# TA-1042-8P8C_V5.net
KiCad netlist of a schematic drawn in EAGLE
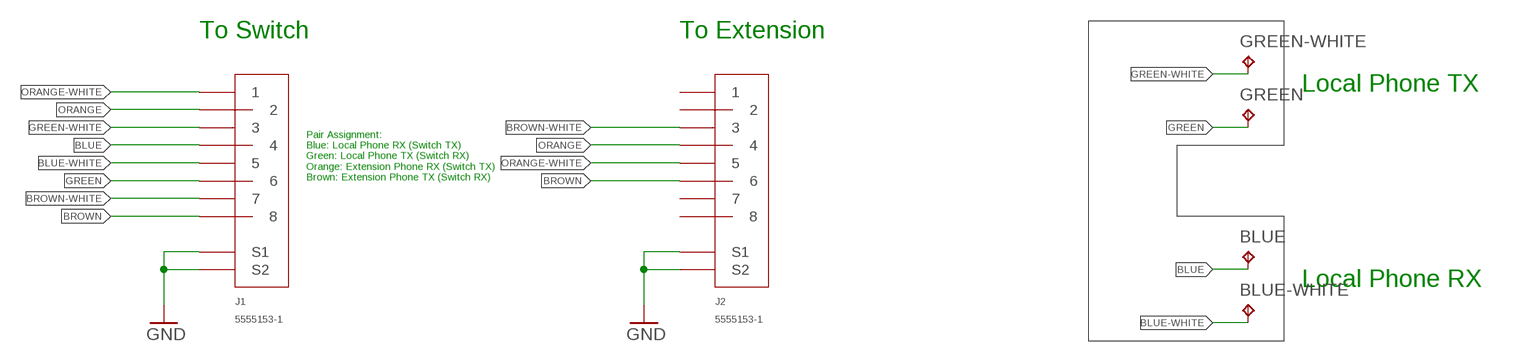
[diagram p0: schematic, sheet 1]

(export (version "E")
  (design (tool "Eeschema 10.0.6"))
  (components
    (comp (ref "BLUE")
      (value "TPTP20R")
      (footprint "eagle-import:TP20R")
      (libsource (lib "eagle-import") (part "TPTP20R"))
    )
    (comp (ref "BLUE-WHITE")
      (value "TPTP20R")
      (footprint "eagle-import:TP20R")
      (libsource (lib "eagle-import") (part "TPTP20R"))
    )
    (comp (ref "GREEN")
      (value "TPTP20R")
      (footprint "eagle-import:TP20R")
      (libsource (lib "eagle-import") (part "TPTP20R"))
    )
    (comp (ref "GREEN-WHITE")
      (value "TPTP20R")
      (footprint "eagle-import:TP20R")
      (libsource (lib "eagle-import") (part "TPTP20R"))
    )
    (comp (ref "J1")
      (value "5555153-1")
      (footprint "eagle-import:5555153-1")
      (fields (field (name "PARTNO") "A31438-ND"))
      (libsource (lib "eagle-import") (part "5555153-1"))
    )
    (comp (ref "J2")
      (value "5555153-1")
      (footprint "eagle-import:5555153-1")
      (fields (field (name "PARTNO") "A31438-ND"))
      (libsource (lib "eagle-import") (part "5555153-1"))
    )
  )
  (nets
    (net (code "1") (name "BLUE") (class "Default")
      (node (ref "BLUE") (pin "TP") (pinfunction "TP_TP") (pintype "input"))
      (node (ref "J1") (pin "4") (pinfunction "4_4") (pintype "bidirectional"))
    )
    (net (code "2") (name "BLUE-WHITE") (class "Default")
      (node (ref "BLUE-WHITE") (pin "TP") (pinfunction "TP_TP") (pintype "input"))
      (node (ref "J1") (pin "5") (pinfunction "5_5") (pintype "bidirectional"))
    )
    (net (code "3") (name "BROWN") (class "Default")
      (node (ref "J1") (pin "8") (pinfunction "8_8") (pintype "bidirectional"))
      (node (ref "J2") (pin "6") (pinfunction "6_6") (pintype "bidirectional"))
    )
    (net (code "4") (name "BROWN-WHITE") (class "Default")
      (node (ref "J1") (pin "7") (pinfunction "7_7") (pintype "bidirectional"))
      (node (ref "J2") (pin "3") (pinfunction "3_3") (pintype "bidirectional"))
    )
    (net (code "5") (name "GND") (class "Default")
      (node (ref "J1") (pin "S1") (pinfunction "S1_S1") (pintype "bidirectional"))
      (node (ref "J1") (pin "S2") (pinfunction "S2_S2") (pintype "bidirectional"))
      (node (ref "J2") (pin "S1") (pinfunction "S1_S1") (pintype "bidirectional"))
      (node (ref "J2") (pin "S2") (pinfunction "S2_S2") (pintype "bidirectional"))
    )
    (net (code "6") (name "GREEN") (class "Default")
      (node (ref "GREEN") (pin "TP") (pinfunction "TP_TP") (pintype "input"))
      (node (ref "J1") (pin "6") (pinfunction "6_6") (pintype "bidirectional"))
    )
    (net (code "7") (name "GREEN-WHITE") (class "Default")
      (node (ref "GREEN-WHITE") (pin "TP") (pinfunction "TP_TP") (pintype "input"))
      (node (ref "J1") (pin "3") (pinfunction "3_3") (pintype "bidirectional"))
    )
    (net (code "8") (name "ORANGE") (class "Default")
      (node (ref "J1") (pin "2") (pinfunction "2_2") (pintype "bidirectional"))
      (node (ref "J2") (pin "4") (pinfunction "4_4") (pintype "bidirectional"))
    )
    (net (code "9") (name "ORANGE-WHITE") (class "Default")
      (node (ref "J1") (pin "1") (pinfunction "1_1") (pintype "bidirectional"))
      (node (ref "J2") (pin "5") (pinfunction "5_5") (pintype "bidirectional"))
    )
    (net (code "10") (name "unconnected-(J2-Pad1)") (class "Default")
      (node (ref "J2") (pin "1") (pinfunction "1_1") (pintype "bidirectional"))
    )
    (net (code "11") (name "unconnected-(J2-Pad2)") (class "Default")
      (node (ref "J2") (pin "2") (pinfunction "2_2") (pintype "bidirectional"))
    )
    (net (code "12") (name "unconnected-(J2-Pad7)") (class "Default")
      (node (ref "J2") (pin "7") (pinfunction "7_7") (pintype "bidirectional"))
    )
    (net (code "13") (name "unconnected-(J2-Pad8)") (class "Default")
      (node (ref "J2") (pin "8") (pinfunction "8_8") (pintype "bidirectional"))
    )
  )
)
